# satshakit_cnc.net
KiCad netlist of a schematic drawn in EAGLE
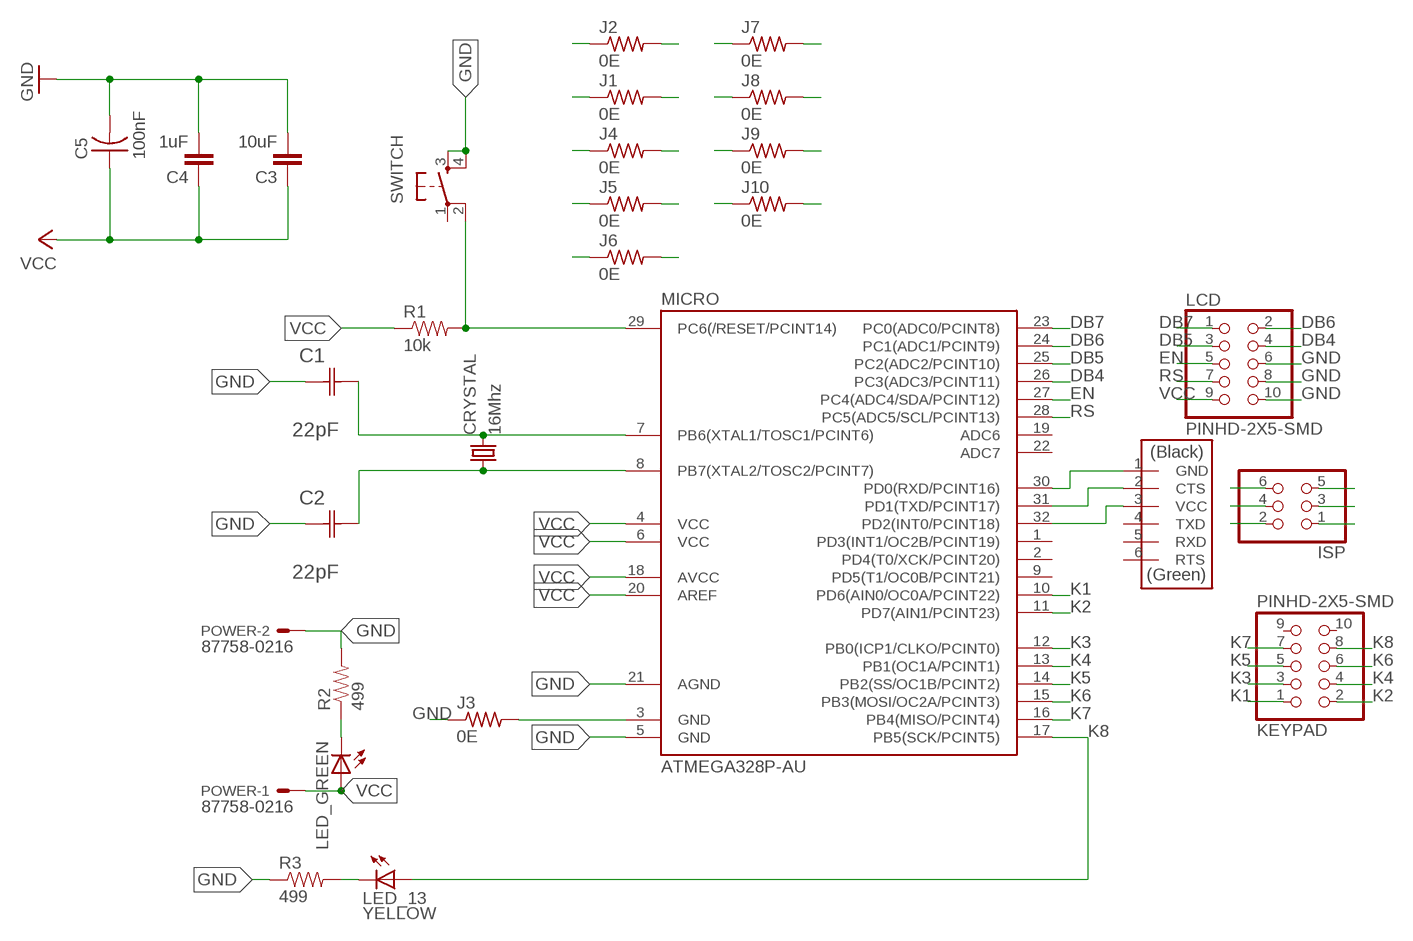
[diagram p0: schematic, sheet 1]

(export (version "E")
  (design (tool "Eeschema 10.0.6"))
  (components
    (comp (ref "C1")
      (value "22pF")
      (footprint "eagle-import:CAPC3216X178N")
      (fields (field (name "MPN") "0612ZC225MAT2A") (field (name "TOLERANCE") "±20%"))
      (libsource (lib "eagle-import") (part "0612ZC225MAT2A"))
    )
    (comp (ref "C2")
      (value "22pF")
      (footprint "eagle-import:CAPC3216X178N")
      (fields (field (name "MPN") "0612ZC225MAT2A") (field (name "TOLERANCE") "±20%"))
      (libsource (lib "eagle-import") (part "0612ZC225MAT2A"))
    )
    (comp (ref "C3")
      (value "10uF")
      (footprint "eagle-import:1206")
      (libsource (lib "eagle-import") (part "CAP1206"))
    )
    (comp (ref "C4")
      (value "1uF")
      (footprint "eagle-import:1206")
      (libsource (lib "eagle-import") (part "CAP1206"))
    )
    (comp (ref "C5")
      (value "100nF")
      (footprint "eagle-import:C1206FAB")
      (libsource (lib "eagle-import") (part "CAP-US1206FAB"))
    )
    (comp (ref "CRYSTAL")
      (value "16Mhz")
      (footprint "eagle-import:CSM-7X-DU")
      (libsource (lib "eagle-import") (part "CSM-7X-DU"))
    )
    (comp (ref "GSM")
      (value "FTDI-SMD-HEADER")
      (footprint "eagle-import:1X06SMD")
      (libsource (lib "eagle-import") (part "FTDI-SMD-HEADER"))
    )
    (comp (ref "ISP")
      (value "PINHD-2X3-SMD")
      (footprint "eagle-import:2X03SMD")
      (libsource (lib "eagle-import") (part "PINHD-2X3-SMD"))
    )
    (comp (ref "J1")
      (value "0E")
      (footprint "eagle-import:R1206FAB")
      (libsource (lib "eagle-import") (part "RES-US1206FAB"))
    )
    (comp (ref "J2")
      (value "0E")
      (footprint "eagle-import:R1206FAB")
      (libsource (lib "eagle-import") (part "RES-US1206FAB"))
    )
    (comp (ref "J3")
      (value "0E")
      (footprint "eagle-import:R1206FAB")
      (libsource (lib "eagle-import") (part "RES-US1206FAB"))
    )
    (comp (ref "J4")
      (value "0E")
      (footprint "eagle-import:R1206FAB")
      (libsource (lib "eagle-import") (part "RES-US1206FAB"))
    )
    (comp (ref "J5")
      (value "0E")
      (footprint "eagle-import:R1206FAB")
      (libsource (lib "eagle-import") (part "RES-US1206FAB"))
    )
    (comp (ref "J6")
      (value "0E")
      (footprint "eagle-import:R1206FAB")
      (libsource (lib "eagle-import") (part "RES-US1206FAB"))
    )
    (comp (ref "J7")
      (value "0E")
      (footprint "eagle-import:R1206FAB")
      (libsource (lib "eagle-import") (part "RES-US1206FAB"))
    )
    (comp (ref "J8")
      (value "0E")
      (footprint "eagle-import:R1206FAB")
      (libsource (lib "eagle-import") (part "RES-US1206FAB"))
    )
    (comp (ref "J9")
      (value "0E")
      (footprint "eagle-import:R1206FAB")
      (libsource (lib "eagle-import") (part "RES-US1206FAB"))
    )
    (comp (ref "J10")
      (value "0E")
      (footprint "eagle-import:R1206FAB")
      (libsource (lib "eagle-import") (part "RES-US1206FAB"))
    )
    (comp (ref "KEYPAD")
      (value "PINHD-2X5-SMD")
      (footprint "eagle-import:2X05SMD")
      (libsource (lib "eagle-import") (part "PINHD-2X5-SMD"))
    )
    (comp (ref "LCD")
      (value "PINHD-2X5-SMD")
      (footprint "eagle-import:2X05SMD")
      (libsource (lib "eagle-import") (part "PINHD-2X5-SMD"))
    )
    (comp (ref "LED_13")
      (value "YELLOW")
      (footprint "eagle-import:1206")
      (libsource (lib "eagle-import") (part "LED1206"))
    )
    (comp (ref "LED_GREEN")
      (value "LED1206")
      (footprint "eagle-import:1206")
      (libsource (lib "eagle-import") (part "LED1206"))
    )
    (comp (ref "MICRO")
      (value "ATMEGA328P-AU")
      (footprint "eagle-import:TQFP32-08")
      (libsource (lib "eagle-import") (part "ATMEGA48/88/168-AU"))
    )
    (comp (ref "POWER")
      (value "87758-0216")
      (footprint "eagle-import:87758-0216")
      (libsource (lib "eagle-import") (part "87758-0216"))
    )
    (comp (ref "R1")
      (value "10k")
      (footprint "eagle-import:1206")
      (libsource (lib "eagle-import") (part "RESISTOR1206"))
    )
    (comp (ref "R2")
      (value "499")
      (footprint "eagle-import:1206")
      (libsource (lib "eagle-import") (part "RESISTOR1206"))
    )
    (comp (ref "R3")
      (value "499")
      (footprint "eagle-import:1206")
      (libsource (lib "eagle-import") (part "RESISTOR1206"))
    )
    (comp (ref "SWITCH")
      (value "6MM_SWITCH6MM_SWITCH")
      (footprint "eagle-import:6MM_SWITCH")
      (libsource (lib "eagle-import") (part "6MM_SWITCH6MM_SWITCH"))
    )
  )
  (nets
    (net (code "1") (name "/DB4") (class "Default")
      (node (ref "LCD") (pin "4") (pinfunction "4_4") (pintype "passive"))
      (node (ref "MICRO") (pin "26") (pinfunction "PC3(ADC3/PCINT11)_26") (pintype "bidirectional"))
    )
    (net (code "2") (name "/DB5") (class "Default")
      (node (ref "LCD") (pin "3") (pinfunction "3_3") (pintype "passive"))
      (node (ref "MICRO") (pin "25") (pinfunction "PC2(ADC2/PCINT10)_25") (pintype "bidirectional"))
    )
    (net (code "3") (name "/DB6") (class "Default")
      (node (ref "LCD") (pin "2") (pinfunction "2_2") (pintype "passive"))
      (node (ref "MICRO") (pin "24") (pinfunction "PC1(ADC1/PCINT9)_24") (pintype "bidirectional"))
    )
    (net (code "4") (name "/DB7") (class "Default")
      (node (ref "LCD") (pin "1") (pinfunction "1_1") (pintype "passive"))
      (node (ref "MICRO") (pin "23") (pinfunction "PC0(ADC0/PCINT8)_23") (pintype "bidirectional"))
    )
    (net (code "5") (name "/EN") (class "Default")
      (node (ref "LCD") (pin "5") (pinfunction "5_5") (pintype "passive"))
      (node (ref "MICRO") (pin "27") (pinfunction "PC4(ADC4/SDA/PCINT12)_27") (pintype "bidirectional"))
    )
    (net (code "6") (name "/K1") (class "Default")
      (node (ref "KEYPAD") (pin "1") (pinfunction "1_1") (pintype "passive"))
      (node (ref "MICRO") (pin "10") (pinfunction "PD6(AIN0/OC0A/PCINT22)_10") (pintype "bidirectional"))
    )
    (net (code "7") (name "/K2") (class "Default")
      (node (ref "KEYPAD") (pin "2") (pinfunction "2_2") (pintype "passive"))
      (node (ref "MICRO") (pin "11") (pinfunction "PD7(AIN1/PCINT23)_11") (pintype "bidirectional"))
    )
    (net (code "8") (name "/K3") (class "Default")
      (node (ref "KEYPAD") (pin "3") (pinfunction "3_3") (pintype "passive"))
      (node (ref "MICRO") (pin "12") (pinfunction "PB0(ICP1/CLKO/PCINT0)_12") (pintype "bidirectional"))
    )
    (net (code "9") (name "/K4") (class "Default")
      (node (ref "KEYPAD") (pin "4") (pinfunction "4_4") (pintype "passive"))
      (node (ref "MICRO") (pin "13") (pinfunction "PB1(OC1A/PCINT1)_13") (pintype "bidirectional"))
    )
    (net (code "10") (name "/K5") (class "Default")
      (node (ref "KEYPAD") (pin "5") (pinfunction "5_5") (pintype "passive"))
      (node (ref "MICRO") (pin "14") (pinfunction "PB2(SS/OC1B/PCINT2)_14") (pintype "bidirectional"))
    )
    (net (code "11") (name "/K6") (class "Default")
      (node (ref "ISP") (pin "4") (pinfunction "4_4") (pintype "passive"))
      (node (ref "KEYPAD") (pin "6") (pinfunction "6_6") (pintype "passive"))
      (node (ref "MICRO") (pin "15") (pinfunction "PB3(MOSI/OC2A/PCINT3)_15") (pintype "bidirectional"))
    )
    (net (code "12") (name "/K7") (class "Default")
      (node (ref "ISP") (pin "1") (pinfunction "1_1") (pintype "passive"))
      (node (ref "J5") (pin "1") (pinfunction "1_1") (pintype "passive"))
      (node (ref "J5") (pin "2") (pinfunction "2_2") (pintype "passive"))
      (node (ref "KEYPAD") (pin "7") (pinfunction "7_7") (pintype "passive"))
      (node (ref "MICRO") (pin "16") (pinfunction "PB4(MISO/PCINT4)_16") (pintype "bidirectional"))
    )
    (net (code "13") (name "/K8") (class "Default")
      (node (ref "ISP") (pin "3") (pinfunction "3_3") (pintype "passive"))
      (node (ref "J4") (pin "1") (pinfunction "1_1") (pintype "passive"))
      (node (ref "J4") (pin "2") (pinfunction "2_2") (pintype "passive"))
      (node (ref "KEYPAD") (pin "8") (pinfunction "8_8") (pintype "passive"))
      (node (ref "LED_13") (pin "1") (pinfunction "A_1") (pintype "passive"))
      (node (ref "MICRO") (pin "17") (pinfunction "PB5(SCK/PCINT5)_17") (pintype "bidirectional"))
    )
    (net (code "14") (name "/RS") (class "Default")
      (node (ref "LCD") (pin "7") (pinfunction "7_7") (pintype "passive"))
      (node (ref "MICRO") (pin "28") (pinfunction "PC5(ADC5/SCL/PCINT13)_28") (pintype "bidirectional"))
    )
    (net (code "15") (name "/RST") (class "Default")
      (node (ref "ISP") (pin "5") (pinfunction "5_5") (pintype "passive"))
      (node (ref "J1") (pin "1") (pinfunction "1_1") (pintype "passive"))
      (node (ref "J1") (pin "2") (pinfunction "2_2") (pintype "passive"))
      (node (ref "J9") (pin "1") (pinfunction "1_1") (pintype "passive"))
      (node (ref "J9") (pin "2") (pinfunction "2_2") (pintype "passive"))
      (node (ref "MICRO") (pin "29") (pinfunction "PC6(/RESET/PCINT14)_29") (pintype "bidirectional"))
      (node (ref "R1") (pin "2") (pinfunction "2_2") (pintype "passive"))
      (node (ref "SWITCH") (pin "2") (pinfunction "P1_2") (pintype "passive"))
    )
    (net (code "16") (name "GND") (class "Default")
      (node (ref "C1") (pin "1") (pinfunction "C1_1") (pintype "passive"))
      (node (ref "C2") (pin "1") (pinfunction "C1_1") (pintype "passive"))
      (node (ref "C3") (pin "2") (pinfunction "2_2") (pintype "passive"))
      (node (ref "C4") (pin "2") (pinfunction "2_2") (pintype "passive"))
      (node (ref "C5") (pin "2") (pinfunction "2_2") (pintype "passive"))
      (node (ref "ISP") (pin "6") (pinfunction "6_6") (pintype "passive"))
      (node (ref "J10") (pin "1") (pinfunction "1_1") (pintype "passive"))
      (node (ref "J10") (pin "2") (pinfunction "2_2") (pintype "passive"))
      (node (ref "J3") (pin "1") (pinfunction "1_1") (pintype "passive"))
      (node (ref "J3") (pin "2") (pinfunction "2_2") (pintype "passive"))
      (node (ref "J8") (pin "1") (pinfunction "1_1") (pintype "passive"))
      (node (ref "J8") (pin "2") (pinfunction "2_2") (pintype "passive"))
      (node (ref "LCD") (pin "10") (pinfunction "10_10") (pintype "passive"))
      (node (ref "LCD") (pin "6") (pinfunction "6_6") (pintype "passive"))
      (node (ref "LCD") (pin "8") (pinfunction "8_8") (pintype "passive"))
      (node (ref "MICRO") (pin "21") (pinfunction "AGND_21") (pintype "power_in"))
      (node (ref "MICRO") (pin "3") (pinfunction "GND_3") (pintype "power_in"))
      (node (ref "MICRO") (pin "5") (pinfunction "GND_5") (pintype "power_in"))
      (node (ref "POWER") (pin "2") (pinfunction "S_2") (pintype "passive"))
      (node (ref "R2") (pin "2") (pinfunction "2_2") (pintype "passive"))
      (node (ref "R3") (pin "1") (pinfunction "1_1") (pintype "passive"))
      (node (ref "SWITCH") (pin "3") (pinfunction "S_3") (pintype "passive"))
      (node (ref "SWITCH") (pin "4") (pinfunction "S1_4") (pintype "passive"))
    )
    (net (code "17") (name "Net-(C1-C2)") (class "Default")
      (node (ref "C1") (pin "2") (pinfunction "C2_2") (pintype "passive"))
      (node (ref "CRYSTAL") (pin "2") (pinfunction "2_2") (pintype "passive"))
      (node (ref "MICRO") (pin "7") (pinfunction "PB6(XTAL1/TOSC1/PCINT6)_7") (pintype "bidirectional"))
    )
    (net (code "18") (name "Net-(C2-C2)") (class "Default")
      (node (ref "C2") (pin "2") (pinfunction "C2_2") (pintype "passive"))
      (node (ref "CRYSTAL") (pin "1") (pinfunction "1_1") (pintype "passive"))
      (node (ref "MICRO") (pin "8") (pinfunction "PB7(XTAL2/TOSC2/PCINT7)_8") (pintype "bidirectional"))
    )
    (net (code "19") (name "Net-(GSM-CTS)") (class "Default")
      (node (ref "GSM") (pin "2") (pinfunction "CTS_2") (pintype "bidirectional"))
      (node (ref "MICRO") (pin "31") (pinfunction "PD1(TXD/PCINT17)_31") (pintype "bidirectional"))
    )
    (net (code "20") (name "Net-(GSM-GND)") (class "Default")
      (node (ref "GSM") (pin "1") (pinfunction "GND_1") (pintype "bidirectional"))
      (node (ref "MICRO") (pin "30") (pinfunction "PD0(RXD/PCINT16)_30") (pintype "bidirectional"))
    )
    (net (code "21") (name "Net-(GSM-VCC)") (class "Default")
      (node (ref "GSM") (pin "3") (pinfunction "VCC_3") (pintype "bidirectional"))
      (node (ref "MICRO") (pin "32") (pinfunction "PD2(INT0/PCINT18)_32") (pintype "bidirectional"))
    )
    (net (code "22") (name "Net-(LED_13-C)") (class "Default")
      (node (ref "LED_13") (pin "2") (pinfunction "C_2") (pintype "passive"))
      (node (ref "R3") (pin "2") (pinfunction "2_2") (pintype "passive"))
    )
    (net (code "23") (name "Net-(LED_GREEN-C)") (class "Default")
      (node (ref "LED_GREEN") (pin "2") (pinfunction "C_2") (pintype "passive"))
      (node (ref "R2") (pin "1") (pinfunction "1_1") (pintype "passive"))
    )
    (net (code "24") (name "VCC") (class "Default")
      (node (ref "C3") (pin "1") (pinfunction "1_1") (pintype "passive"))
      (node (ref "C4") (pin "1") (pinfunction "1_1") (pintype "passive"))
      (node (ref "C5") (pin "1") (pinfunction "1_1") (pintype "passive"))
      (node (ref "ISP") (pin "2") (pinfunction "2_2") (pintype "passive"))
      (node (ref "J2") (pin "1") (pinfunction "1_1") (pintype "passive"))
      (node (ref "J2") (pin "2") (pinfunction "2_2") (pintype "passive"))
      (node (ref "J6") (pin "1") (pinfunction "1_1") (pintype "passive"))
      (node (ref "J6") (pin "2") (pinfunction "2_2") (pintype "passive"))
      (node (ref "J7") (pin "1") (pinfunction "1_1") (pintype "passive"))
      (node (ref "J7") (pin "2") (pinfunction "2_2") (pintype "passive"))
      (node (ref "LCD") (pin "9") (pinfunction "9_9") (pintype "passive"))
      (node (ref "LED_GREEN") (pin "1") (pinfunction "A_1") (pintype "passive"))
      (node (ref "MICRO") (pin "18") (pinfunction "AVCC_18") (pintype "passive"))
      (node (ref "MICRO") (pin "20") (pinfunction "AREF_20") (pintype "passive"))
      (node (ref "MICRO") (pin "4") (pinfunction "VCC_4") (pintype "power_in"))
      (node (ref "MICRO") (pin "6") (pinfunction "VCC_6") (pintype "power_in"))
      (node (ref "POWER") (pin "1") (pinfunction "S_1") (pintype "passive"))
      (node (ref "R1") (pin "1") (pinfunction "1_1") (pintype "passive"))
    )
    (net (code "25") (name "unconnected-(GSM-RTS-Pad6)") (class "Default")
      (node (ref "GSM") (pin "6") (pinfunction "RTS_6") (pintype "bidirectional"))
    )
    (net (code "26") (name "unconnected-(GSM-RXD-Pad5)") (class "Default")
      (node (ref "GSM") (pin "5") (pinfunction "RXD_5") (pintype "bidirectional"))
    )
    (net (code "27") (name "unconnected-(GSM-TXD-Pad4)") (class "Default")
      (node (ref "GSM") (pin "4") (pinfunction "TXD_4") (pintype "bidirectional"))
    )
    (net (code "28") (name "unconnected-(KEYPAD-Pad9)") (class "Default")
      (node (ref "KEYPAD") (pin "9") (pinfunction "9_9") (pintype "passive"))
    )
    (net (code "29") (name "unconnected-(KEYPAD-Pad10)") (class "Default")
      (node (ref "KEYPAD") (pin "10") (pinfunction "10_10") (pintype "passive"))
    )
    (net (code "30") (name "unconnected-(MICRO-ADC6-Pad19)") (class "Default")
      (node (ref "MICRO") (pin "19") (pinfunction "ADC6_19") (pintype "passive"))
    )
    (net (code "31") (name "unconnected-(MICRO-ADC7-Pad22)") (class "Default")
      (node (ref "MICRO") (pin "22") (pinfunction "ADC7_22") (pintype "passive"))
    )
    (net (code "32") (name "unconnected-(MICRO-PD3(INT1{slash}OC2B{slash}PCINT19)-Pad1)") (class "Default")
      (node (ref "MICRO") (pin "1") (pinfunction "PD3(INT1/OC2B/PCINT19)_1") (pintype "bidirectional"))
    )
    (net (code "33") (name "unconnected-(MICRO-PD4(T0{slash}XCK{slash}PCINT20)-Pad2)") (class "Default")
      (node (ref "MICRO") (pin "2") (pinfunction "PD4(T0/XCK/PCINT20)_2") (pintype "bidirectional"))
    )
    (net (code "34") (name "unconnected-(MICRO-PD5(T1{slash}OC0B{slash}PCINT21)-Pad9)") (class "Default")
      (node (ref "MICRO") (pin "9") (pinfunction "PD5(T1/OC0B/PCINT21)_9") (pintype "bidirectional"))
    )
    (net (code "35") (name "unconnected-(SWITCH-P-Pad1)") (class "Default")
      (node (ref "SWITCH") (pin "1") (pinfunction "P_1") (pintype "passive"))
    )
  )
)
